# 07_V5_LED.net
KiCad netlist of a schematic drawn in Altium Designer
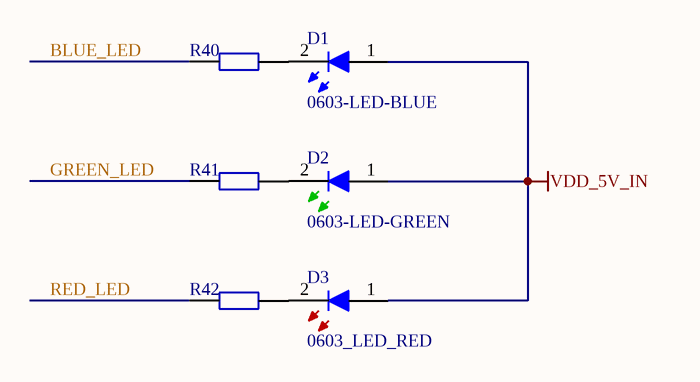
[diagram p0: 07_V5_LED.SchDoc]

(export (version "E")
  (design (tool "Eeschema 10.0.6"))
  (components
    (comp (ref "D1")
      (value "0603-LED-BLUE")
      (footprint "0603-LED-blue")
      (libsource (lib "CUAV") (part "0603-LED-BLUE"))
    )
    (comp (ref "D2")
      (value "0603-LED-GREEN")
      (footprint "0603-LED-Green")
      (libsource (lib "CUAV") (part "0603-LED-GREEN"))
    )
    (comp (ref "D3")
      (value "0603_LED_RED")
      (footprint "0603-LED-RED")
      (libsource (lib "CUAV") (part "0603_LED_RED"))
    )
    (comp (ref "R40")
      (value "1K")
      (footprint "0402R")
      (description "0402R100R 1%")
      (libsource (lib "CUAV") (part "0402R100R"))
    )
    (comp (ref "R41")
      (value "1K")
      (footprint "0402R")
      (description "0402R100R 1%")
      (libsource (lib "CUAV") (part "0402R100R"))
    )
    (comp (ref "R42")
      (value "1K")
      (footprint "0402R")
      (description "0402R100R 1%")
      (libsource (lib "CUAV") (part "0402R100R"))
    )
  )
  (nets
    (net (code "1") (name "/BLUE_LED") (class "Default") (node (ref "R40") (pin "1") (pintype "passive")))
    (net (code "2") (name "/GREEN_LED") (class "Default") (node (ref "R41") (pin "1") (pintype "passive")))
    (net (code "3") (name "/RED_LED") (class "Default") (node (ref "R42") (pin "1") (pintype "passive")))
    (net (code "4") (name "Net-(D1-Pad2)") (class "Default")
      (node (ref "D1") (pin "2") (pintype "passive"))
      (node (ref "R40") (pin "2") (pintype "passive"))
    )
    (net (code "5") (name "Net-(D2-Pad2)") (class "Default")
      (node (ref "D2") (pin "2") (pintype "passive"))
      (node (ref "R41") (pin "2") (pintype "passive"))
    )
    (net (code "6") (name "Net-(D3-Pad2)") (class "Default")
      (node (ref "D3") (pin "2") (pintype "passive"))
      (node (ref "R42") (pin "2") (pintype "passive"))
    )
    (net (code "7") (name "VDD_5V_IN") (class "Default")
      (node (ref "D1") (pin "1") (pintype "passive"))
      (node (ref "D2") (pin "1") (pintype "passive"))
      (node (ref "D3") (pin "1") (pintype "passive"))
    )
  )
)
